# Receiver_RF_Amplifier_Stage.net
KiCad netlist of a schematic drawn in EAGLE
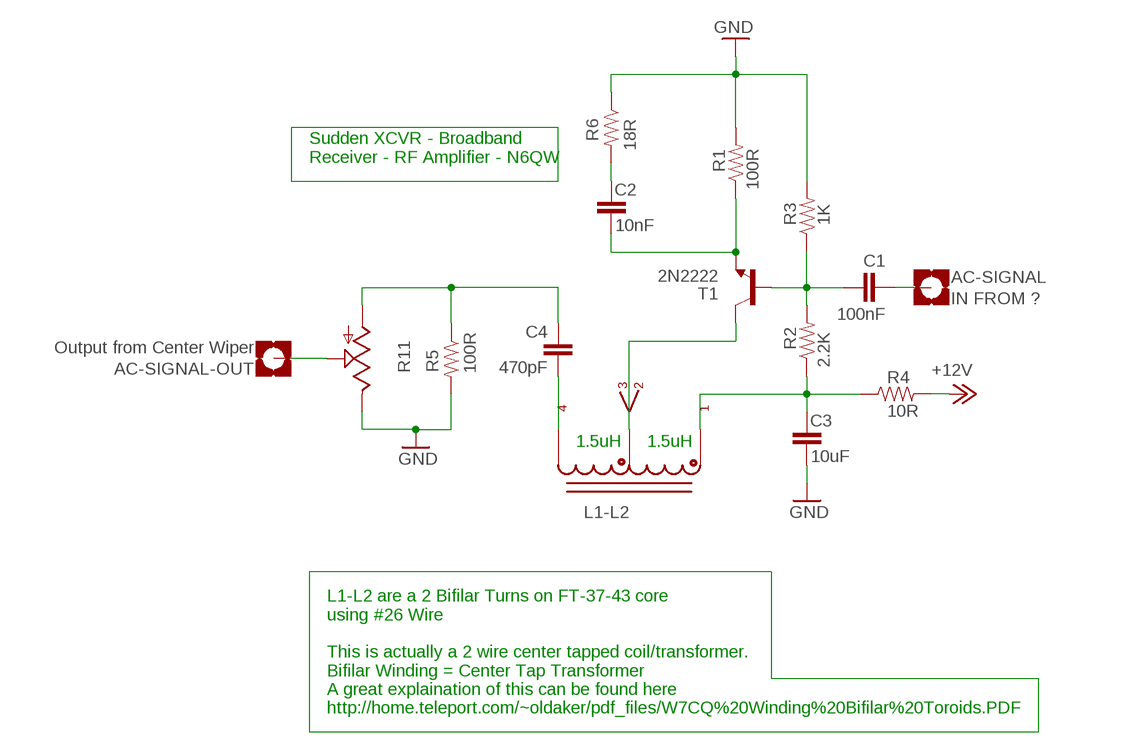
[diagram p0: schematic, sheet 1]

(export (version "E")
  (design (tool "Eeschema 10.0.6"))
  (components
    (comp (ref "AC-SIGNAL")
      (value "IN FROM ?")
      (footprint "eagle-import:PAD-SQUARE")
      (fields (field (name "SPICEPREFIX") "A"))
      (libsource (lib "eagle-import") (part "MOUNT-PAD-SQUARE4.5"))
    )
    (comp (ref "AC-SIGNAL-OUT")
      (value "Output from Center Wiper")
      (footprint "eagle-import:PAD-SQUARE")
      (libsource (lib "eagle-import") (part "MOUNT-PAD-SQUARE4.5"))
    )
    (comp (ref "C1")
      (value "100nF")
      (footprint "eagle-import:CAP-MEDIUM-MUPPET")
      (libsource (lib "eagle-import") (part "CAP-MEDIUM-MUPPET"))
    )
    (comp (ref "C2")
      (value "10nF")
      (footprint "eagle-import:CAP-MEDIUM-MUPPET")
      (libsource (lib "eagle-import") (part "CAP-MEDIUM-MUPPET"))
    )
    (comp (ref "C3")
      (value "10uF")
      (footprint "eagle-import:CAP-MEDIUM-MUPPET")
      (libsource (lib "eagle-import") (part "CAP-MEDIUM-MUPPET"))
    )
    (comp (ref "C4")
      (value "470pF")
      (footprint "eagle-import:CAP-MEDIUM-MUPPET")
      (libsource (lib "eagle-import") (part "CAP-MEDIUM-MUPPET"))
    )
    (comp (ref "L1-L2")
      (value "T37-43_BIFILAR_TORIODBIFILAR-COIL/TRANSFORMER")
      (footprint "eagle-import:T37-43_BIFILAR_TOROID")
      (libsource (lib "eagle-import") (part "T37-43_BIFILAR_TORIODBIFILAR-COIL/TRANSFORMER"))
    )
    (comp (ref "P+1")
      (value "+12V")
      (footprint "eagle-import:POWER-IN-PAD")
      (libsource (lib "eagle-import") (part "+12V"))
    )
    (comp (ref "R1")
      (value "100R")
      (footprint "eagle-import:RESITOR-MUPPET")
      (libsource (lib "eagle-import") (part "RESISTOR-MUPPETMEDIUM-RESISTOR-PADS"))
    )
    (comp (ref "R2")
      (value "2.2K")
      (footprint "eagle-import:RESITOR-MUPPET")
      (libsource (lib "eagle-import") (part "RESISTOR-MUPPETMEDIUM-RESISTOR-PADS"))
    )
    (comp (ref "R3")
      (value "1K")
      (footprint "eagle-import:RESITOR-MUPPET")
      (libsource (lib "eagle-import") (part "RESISTOR-MUPPETMEDIUM-RESISTOR-PADS"))
    )
    (comp (ref "R4")
      (value "10R")
      (footprint "eagle-import:RESITOR-MUPPET")
      (libsource (lib "eagle-import") (part "RESISTOR-MUPPETMEDIUM-RESISTOR-PADS"))
    )
    (comp (ref "R5")
      (value "100R")
      (footprint "eagle-import:RESITOR-MUPPET")
      (libsource (lib "eagle-import") (part "RESISTOR-MUPPETMEDIUM-RESISTOR-PADS"))
    )
    (comp (ref "R6")
      (value "18R")
      (footprint "eagle-import:RESITOR-MUPPET")
      (libsource (lib "eagle-import") (part "RESISTOR-MUPPETMEDIUM-RESISTOR-PADS"))
    )
    (comp (ref "R11")
      (value "POTENTIOMETER-TRIMCT6")
      (footprint "eagle-import:POT-TRIMM-4")
      (libsource (lib "eagle-import") (part "POTENTIOMETER-TRIMCT6"))
    )
    (comp (ref "T1")
      (value "2N2222")
      (footprint "eagle-import:2N2222-TO18")
      (libsource (lib "eagle-import") (part "2N2222"))
    )
  )
  (nets
    (net (code "1") (name "+12V") (class "Default")
      (node (ref "P+1") (pin "VCC") (pinfunction "+12V_VCC") (pintype "power_in"))
      (node (ref "R4") (pin "P$2") (pinfunction "2_P$2") (pintype "passive"))
    )
    (net (code "2") (name "GND") (class "Default")
      (node (ref "C3") (pin "1") (pinfunction "1_1") (pintype "passive"))
      (node (ref "R1") (pin "P$2") (pinfunction "2_P$2") (pintype "passive"))
      (node (ref "R11") (pin "E") (pinfunction "E_E") (pintype "passive"))
      (node (ref "R3") (pin "P$2") (pinfunction "2_P$2") (pintype "passive"))
      (node (ref "R5") (pin "P$2") (pinfunction "2_P$2") (pintype "passive"))
      (node (ref "R6") (pin "P$1") (pinfunction "1_P$1") (pintype "passive"))
    )
    (net (code "3") (name "Net-(AC-SIGNAL-MOUNT)") (class "Default")
      (node (ref "AC-SIGNAL") (pin "PAD") (pinfunction "MOUNT_PAD") (pintype "passive"))
      (node (ref "C1") (pin "2") (pinfunction "2_2") (pintype "passive"))
    )
    (net (code "4") (name "Net-(AC-SIGNAL-OUT-MOUNT)") (class "Default")
      (node (ref "AC-SIGNAL-OUT") (pin "PAD") (pinfunction "MOUNT_PAD") (pintype "passive"))
      (node (ref "R11") (pin "S") (pinfunction "S_S") (pintype "passive"))
    )
    (net (code "5") (name "Net-(C4-Pad1)") (class "Default")
      (node (ref "C4") (pin "1") (pinfunction "1_1") (pintype "passive"))
      (node (ref "L1-L2") (pin "C3A") (pinfunction "C3A_C3A") (pintype "bidirectional"))
    )
    (net (code "6") (name "Net-(R1-1)") (class "Default")
      (node (ref "C2") (pin "1") (pinfunction "1_1") (pintype "passive"))
      (node (ref "R1") (pin "P$1") (pinfunction "1_P$1") (pintype "passive"))
      (node (ref "T1") (pin "1") (pinfunction "E_1") (pintype "passive"))
    )
    (net (code "7") (name "Net-(R2-1)") (class "Default")
      (node (ref "C3") (pin "2") (pinfunction "2_2") (pintype "passive"))
      (node (ref "L1-L2") (pin "C1A") (pinfunction "C1A_C1A") (pintype "bidirectional"))
      (node (ref "R2") (pin "P$1") (pinfunction "1_P$1") (pintype "passive"))
      (node (ref "R4") (pin "P$1") (pinfunction "1_P$1") (pintype "passive"))
    )
    (net (code "8") (name "Net-(R2-2)") (class "Default")
      (node (ref "C1") (pin "1") (pinfunction "1_1") (pintype "passive"))
      (node (ref "R2") (pin "P$2") (pinfunction "2_P$2") (pintype "passive"))
      (node (ref "R3") (pin "P$1") (pinfunction "1_P$1") (pintype "passive"))
      (node (ref "T1") (pin "2") (pinfunction "B_2") (pintype "passive"))
    )
    (net (code "9") (name "Net-(R5-1)") (class "Default")
      (node (ref "C4") (pin "2") (pinfunction "2_2") (pintype "passive"))
      (node (ref "R11") (pin "A") (pinfunction "A_A") (pintype "passive"))
      (node (ref "R5") (pin "P$1") (pinfunction "1_P$1") (pintype "passive"))
    )
    (net (code "10") (name "Net-(R6-2)") (class "Default")
      (node (ref "C2") (pin "2") (pinfunction "2_2") (pintype "passive"))
      (node (ref "R6") (pin "P$2") (pinfunction "2_P$2") (pintype "passive"))
    )
    (net (code "11") (name "Net-(T1-C)") (class "Default")
      (node (ref "L1-L2") (pin "C2A") (pinfunction "C2A_C2A") (pintype "bidirectional"))
      (node (ref "T1") (pin "3") (pinfunction "C_3") (pintype "passive"))
    )
  )
)
